# 06_DDR_CONTROLLER.net
KiCad netlist of a schematic drawn in Altium Designer
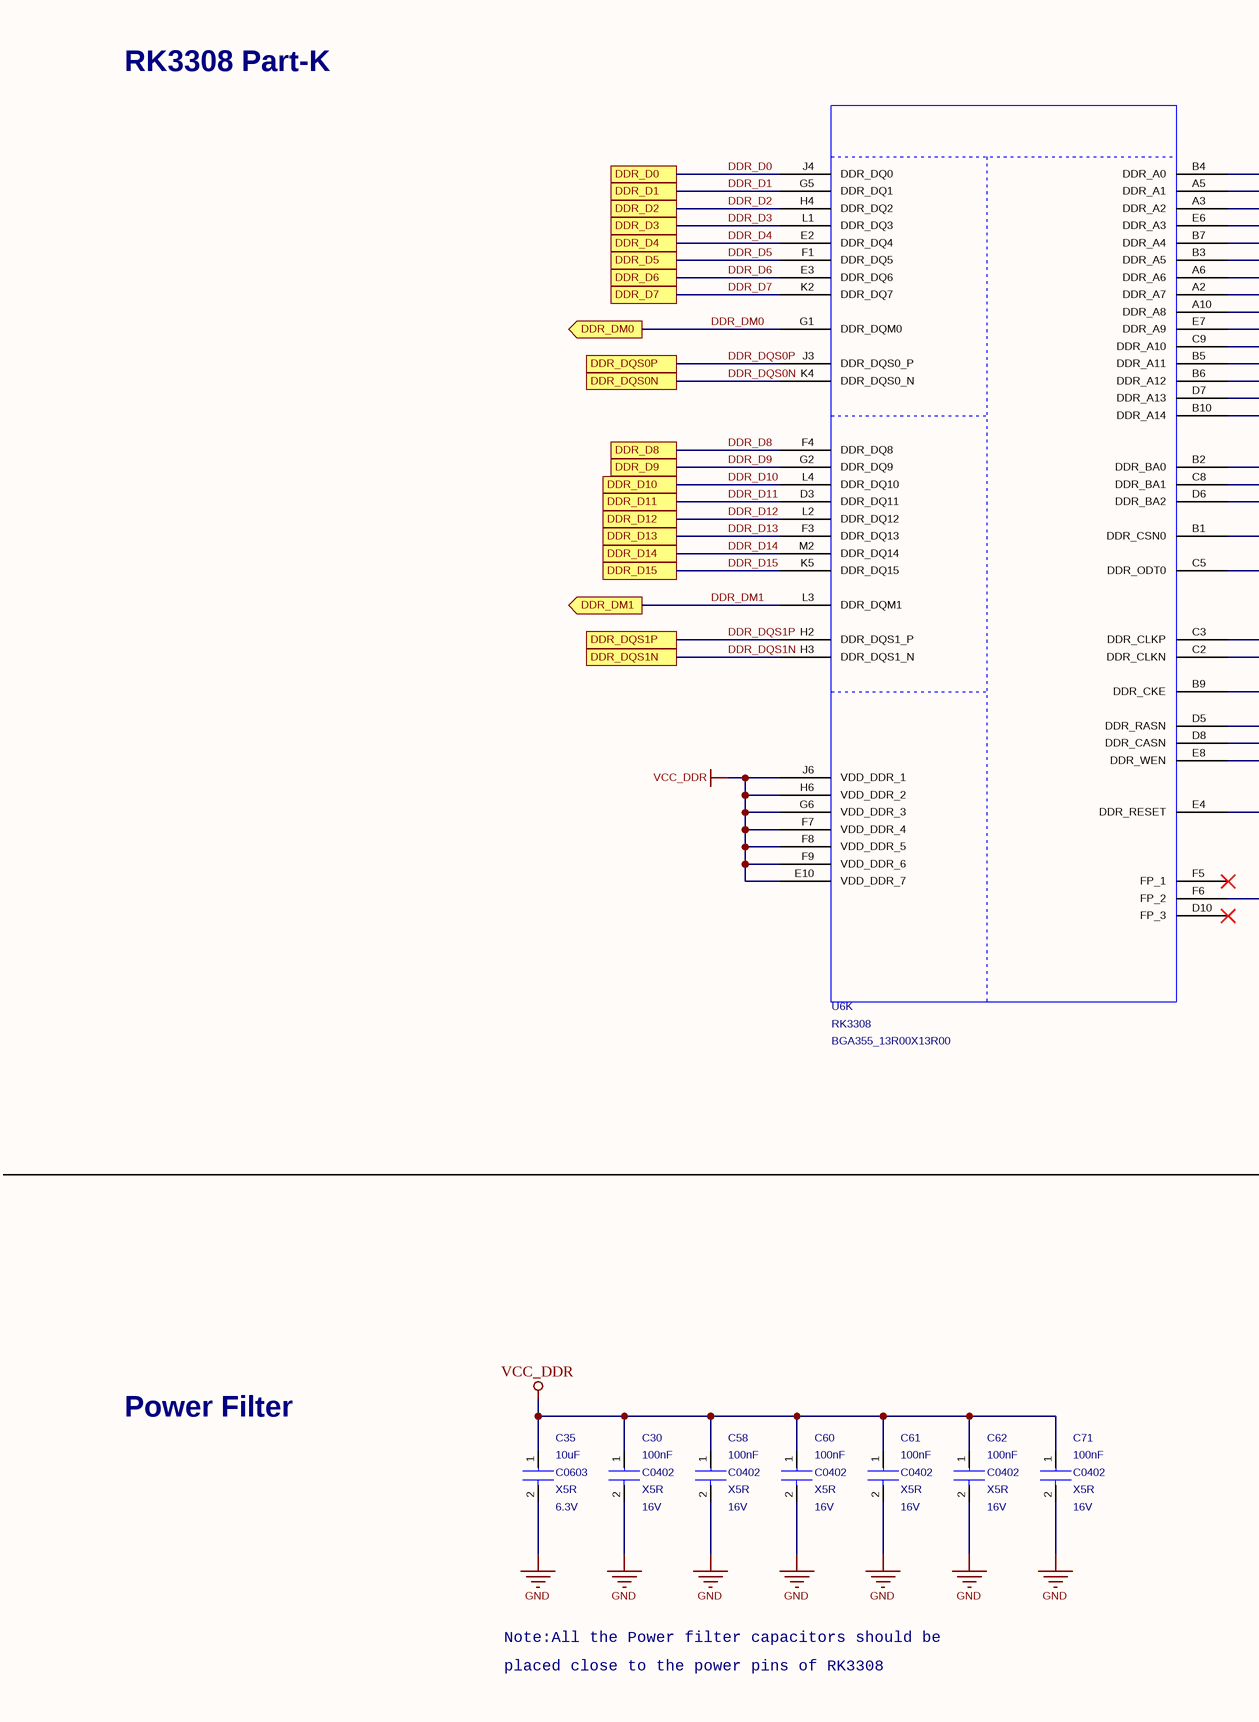
[diagram p0: 06_DDR_CONTROLLER.SchDoc, left]
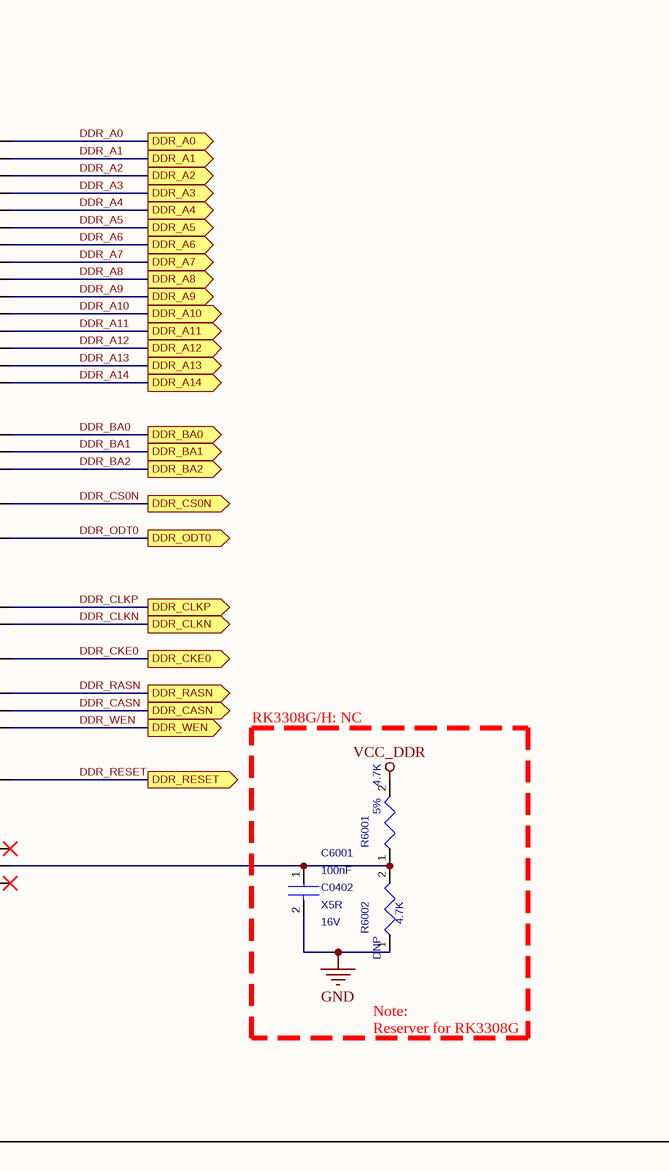
[diagram p1: 06_DDR_CONTROLLER.SchDoc, right]

(export (version "E")
  (design (tool "Eeschema 10.0.6"))
  (components
    (comp (ref "C30")
      (value "100nF")
      (footprint "C0402")
      (description "cap,100.00nF,+/-10%,16V,X5R,C0402")
      (fields
        (field (name "PCB DECAL") "C0402")
        (field (name "MANUFACTURER") "TDK")
        (field (name "TOLERANCE") "10%")
        (field (name "VOLTAGE") "16V")
        (field (name "DIELECTRIC") "X5R")
        (field (name "CREATED_BY") "JJJ")
      )
      (libsource (lib "*") (part "CAP_NP_2"))
    )
    (comp (ref "C35")
      (value "10uF")
      (footprint "C0603")
      (description "cap,10.00uF,+/-10%,6.3V,X5R,C0603")
      (fields
        (field (name "PCB DECAL") "C0603")
        (field (name "DIELECTRIC") "X5R")
        (field (name "VOLTAGE") "6.3V")
        (field (name "TOLERANCE") "10%")
        (field (name "MANUFACTURER") "TDK")
        (field (name "CREATED_BY") "JJJ")
      )
      (libsource (lib "*") (part "CAP_NP_2"))
    )
    (comp (ref "C58")
      (value "100nF")
      (footprint "C0402")
      (description "cap,100.00nF,+/-10%,16V,X5R,C0402")
      (fields
        (field (name "PCB DECAL") "C0402")
        (field (name "DIELECTRIC") "X5R")
        (field (name "VOLTAGE") "16V")
        (field (name "TOLERANCE") "10%")
        (field (name "MANUFACTURER") "TDK")
        (field (name "CREATED_BY") "JJJ")
      )
      (libsource (lib "*") (part "CAP_NP_2"))
    )
    (comp (ref "C60")
      (value "100nF")
      (footprint "C0402")
      (description "cap,100.00nF,+/-10%,16V,X5R,C0402")
      (fields
        (field (name "PCB DECAL") "C0402")
        (field (name "MANUFACTURER") "TDK")
        (field (name "TOLERANCE") "10%")
        (field (name "VOLTAGE") "16V")
        (field (name "DIELECTRIC") "X5R")
        (field (name "CREATED_BY") "JJJ")
      )
      (libsource (lib "*") (part "CAP_NP_2"))
    )
    (comp (ref "C61")
      (value "100nF")
      (footprint "C0402")
      (description "cap,100.00nF,+/-10%,16V,X5R,C0402")
      (fields
        (field (name "PCB DECAL") "C0402")
        (field (name "MANUFACTURER") "TDK")
        (field (name "TOLERANCE") "10%")
        (field (name "VOLTAGE") "16V")
        (field (name "DIELECTRIC") "X5R")
        (field (name "CREATED_BY") "JJJ")
      )
      (libsource (lib "*") (part "CAP_NP_2"))
    )
    (comp (ref "C62")
      (value "100nF")
      (footprint "C0402")
      (description "cap,100.00nF,+/-10%,16V,X5R,C0402")
      (fields
        (field (name "PCB DECAL") "C0402")
        (field (name "MANUFACTURER") "TDK")
        (field (name "TOLERANCE") "10%")
        (field (name "VOLTAGE") "16V")
        (field (name "DIELECTRIC") "X5R")
        (field (name "CREATED_BY") "JJJ")
      )
      (libsource (lib "*") (part "CAP_NP_2"))
    )
    (comp (ref "C71")
      (value "100nF")
      (footprint "C0402")
      (description "cap,100.00nF,+/-10%,16V,X5R,C0402")
      (fields
        (field (name "PCB DECAL") "C0402")
        (field (name "MANUFACTURER") "TDK")
        (field (name "TOLERANCE") "10%")
        (field (name "VOLTAGE") "16V")
        (field (name "DIELECTRIC") "X5R")
        (field (name "CREATED_BY") "JJJ")
      )
      (libsource (lib "*") (part "CAP_NP_2"))
    )
    (comp (ref "C6001")
      (value "100nF")
      (footprint "C0402")
      (description "cap,100.00nF,+/-10%,16V,X5R,C0402")
      (fields
        (field (name "PCB DECAL") "C0402")
        (field (name "MANUFACTURER") "TDK")
        (field (name "TOLERANCE") "10%")
        (field (name "VOLTAGE") "16V")
        (field (name "DIELECTRIC") "X5R")
        (field (name "CREATED_BY") "JJJ")
      )
      (libsource (lib "*") (part "CAP_NP_2"))
    )
    (comp (ref "R6001")
      (value "4.7K")
      (footprint "R0402")
      (description "?用厚膜电阻,4K7,+/-5%,R0402,1/16W.")
      (fields
        (field (name "MANUFACTURER") "YAGEO")
        (field (name "TOLERANCE") "5%")
        (field (name "CREATED_BY") "YTL")
      )
      (libsource (lib "*") (part "RESISTOR"))
    )
    (comp (ref "R6002")
      (value "4.7K")
      (footprint "R0402")
      (description "?用厚膜电阻,4K7,+/-5%,R0402,1/16W.")
      (fields
        (field (name "MANUFACTURER") "YAGEO")
        (field (name "TOLERANCE") "5%")
        (field (name "OPTION") "DNP")
        (field (name "Comment") "RESISTOR")
        (field (name "CREATED_BY") "YTL")
      )
      (libsource (lib "*") (part "RESISTOR"))
    )
    (comp (ref "U6")
      (value "RK3308")
      (footprint "BGA355_13R00X13R00")
      (fields (field (name "PCB DECAL") "BGA355_13R00X13R00") (field (name "MANUFACTURER") "ROCKCHIP"))
      (libsource (lib "*") (part "RK3308"))
    )
  )
  (nets
    (net (code "1") (name "/DDR_A0") (class "Default")
      (node (ref "U6") (pin "B4") (pinfunction "DDR_A0_B4") (pintype "passive"))
    )
    (net (code "2") (name "/DDR_A1") (class "Default")
      (node (ref "U6") (pin "A5") (pinfunction "DDR_A1_A5") (pintype "passive"))
    )
    (net (code "3") (name "/DDR_A2") (class "Default")
      (node (ref "U6") (pin "A3") (pinfunction "DDR_A2_A3") (pintype "passive"))
    )
    (net (code "4") (name "/DDR_A3") (class "Default")
      (node (ref "U6") (pin "E6") (pinfunction "DDR_A3_E6") (pintype "passive"))
    )
    (net (code "5") (name "/DDR_A4") (class "Default")
      (node (ref "U6") (pin "B7") (pinfunction "DDR_A4_B7") (pintype "passive"))
    )
    (net (code "6") (name "/DDR_A5") (class "Default")
      (node (ref "U6") (pin "B3") (pinfunction "DDR_A5_B3") (pintype "passive"))
    )
    (net (code "7") (name "/DDR_A6") (class "Default")
      (node (ref "U6") (pin "A6") (pinfunction "DDR_A6_A6") (pintype "passive"))
    )
    (net (code "8") (name "/DDR_A7") (class "Default")
      (node (ref "U6") (pin "A2") (pinfunction "DDR_A7_A2") (pintype "passive"))
    )
    (net (code "9") (name "/DDR_A8") (class "Default")
      (node (ref "U6") (pin "A10") (pinfunction "DDR_A8_A10") (pintype "passive"))
    )
    (net (code "10") (name "/DDR_A9") (class "Default")
      (node (ref "U6") (pin "E7") (pinfunction "DDR_A9_E7") (pintype "passive"))
    )
    (net (code "11") (name "/DDR_A10") (class "Default")
      (node (ref "U6") (pin "C9") (pinfunction "DDR_A10_C9") (pintype "passive"))
    )
    (net (code "12") (name "/DDR_A11") (class "Default")
      (node (ref "U6") (pin "B5") (pinfunction "DDR_A11_B5") (pintype "passive"))
    )
    (net (code "13") (name "/DDR_A12") (class "Default")
      (node (ref "U6") (pin "B6") (pinfunction "DDR_A12_B6") (pintype "passive"))
    )
    (net (code "14") (name "/DDR_A13") (class "Default")
      (node (ref "U6") (pin "D7") (pinfunction "DDR_A13_D7") (pintype "passive"))
    )
    (net (code "15") (name "/DDR_A14") (class "Default")
      (node (ref "U6") (pin "B10") (pinfunction "DDR_A14_B10") (pintype "passive"))
    )
    (net (code "16") (name "/DDR_BA0") (class "Default")
      (node (ref "U6") (pin "B2") (pinfunction "DDR_BA0_B2") (pintype "passive"))
    )
    (net (code "17") (name "/DDR_BA1") (class "Default")
      (node (ref "U6") (pin "C8") (pinfunction "DDR_BA1_C8") (pintype "passive"))
    )
    (net (code "18") (name "/DDR_BA2") (class "Default")
      (node (ref "U6") (pin "D6") (pinfunction "DDR_BA2_D6") (pintype "passive"))
    )
    (net (code "19") (name "/DDR_CASN") (class "Default")
      (node (ref "U6") (pin "D8") (pinfunction "DDR_CASN_D8") (pintype "passive"))
    )
    (net (code "20") (name "/DDR_CKE0") (class "Default")
      (node (ref "U6") (pin "B9") (pinfunction "DDR_CKE_B9") (pintype "passive"))
    )
    (net (code "21") (name "/DDR_CLKN") (class "Default")
      (node (ref "U6") (pin "C2") (pinfunction "DDR_CLKN_C2") (pintype "passive"))
    )
    (net (code "22") (name "/DDR_CLKP") (class "Default")
      (node (ref "U6") (pin "C3") (pinfunction "DDR_CLKP_C3") (pintype "passive"))
    )
    (net (code "23") (name "/DDR_CS0N") (class "Default")
      (node (ref "U6") (pin "B1") (pinfunction "DDR_CSN0_B1") (pintype "passive"))
    )
    (net (code "24") (name "/DDR_D0") (class "Default")
      (node (ref "U6") (pin "J4") (pinfunction "DDR_DQ0_J4") (pintype "passive"))
    )
    (net (code "25") (name "/DDR_D1") (class "Default")
      (node (ref "U6") (pin "G5") (pinfunction "DDR_DQ1_G5") (pintype "passive"))
    )
    (net (code "26") (name "/DDR_D2") (class "Default")
      (node (ref "U6") (pin "H4") (pinfunction "DDR_DQ2_H4") (pintype "passive"))
    )
    (net (code "27") (name "/DDR_D3") (class "Default")
      (node (ref "U6") (pin "L1") (pinfunction "DDR_DQ3_L1") (pintype "passive"))
    )
    (net (code "28") (name "/DDR_D4") (class "Default")
      (node (ref "U6") (pin "E2") (pinfunction "DDR_DQ4_E2") (pintype "passive"))
    )
    (net (code "29") (name "/DDR_D5") (class "Default")
      (node (ref "U6") (pin "F1") (pinfunction "DDR_DQ5_F1") (pintype "passive"))
    )
    (net (code "30") (name "/DDR_D6") (class "Default")
      (node (ref "U6") (pin "E3") (pinfunction "DDR_DQ6_E3") (pintype "passive"))
    )
    (net (code "31") (name "/DDR_D7") (class "Default")
      (node (ref "U6") (pin "K2") (pinfunction "DDR_DQ7_K2") (pintype "passive"))
    )
    (net (code "32") (name "/DDR_D8") (class "Default")
      (node (ref "U6") (pin "F4") (pinfunction "DDR_DQ8_F4") (pintype "passive"))
    )
    (net (code "33") (name "/DDR_D9") (class "Default")
      (node (ref "U6") (pin "G2") (pinfunction "DDR_DQ9_G2") (pintype "passive"))
    )
    (net (code "34") (name "/DDR_D10") (class "Default")
      (node (ref "U6") (pin "L4") (pinfunction "DDR_DQ10_L4") (pintype "passive"))
    )
    (net (code "35") (name "/DDR_D11") (class "Default")
      (node (ref "U6") (pin "D3") (pinfunction "DDR_DQ11_D3") (pintype "passive"))
    )
    (net (code "36") (name "/DDR_D12") (class "Default")
      (node (ref "U6") (pin "L2") (pinfunction "DDR_DQ12_L2") (pintype "passive"))
    )
    (net (code "37") (name "/DDR_D13") (class "Default")
      (node (ref "U6") (pin "F3") (pinfunction "DDR_DQ13_F3") (pintype "passive"))
    )
    (net (code "38") (name "/DDR_D14") (class "Default")
      (node (ref "U6") (pin "M2") (pinfunction "DDR_DQ14_M2") (pintype "passive"))
    )
    (net (code "39") (name "/DDR_D15") (class "Default")
      (node (ref "U6") (pin "K5") (pinfunction "DDR_DQ15_K5") (pintype "passive"))
    )
    (net (code "40") (name "/DDR_DM0") (class "Default")
      (node (ref "U6") (pin "G1") (pinfunction "DDR_DQM0_G1") (pintype "passive"))
    )
    (net (code "41") (name "/DDR_DM1") (class "Default")
      (node (ref "U6") (pin "L3") (pinfunction "DDR_DQM1_L3") (pintype "passive"))
    )
    (net (code "42") (name "/DDR_DQS0N") (class "Default")
      (node (ref "U6") (pin "K4") (pinfunction "DDR_DQS0_N_K4") (pintype "passive"))
    )
    (net (code "43") (name "/DDR_DQS0P") (class "Default")
      (node (ref "U6") (pin "J3") (pinfunction "DDR_DQS0_P_J3") (pintype "passive"))
    )
    (net (code "44") (name "/DDR_DQS1N") (class "Default")
      (node (ref "U6") (pin "H3") (pinfunction "DDR_DQS1_N_H3") (pintype "passive"))
    )
    (net (code "45") (name "/DDR_DQS1P") (class "Default")
      (node (ref "U6") (pin "H2") (pinfunction "DDR_DQS1_P_H2") (pintype "passive"))
    )
    (net (code "46") (name "/DDR_ODT0") (class "Default")
      (node (ref "U6") (pin "C5") (pinfunction "DDR_ODT0_C5") (pintype "passive"))
    )
    (net (code "47") (name "/DDR_RASN") (class "Default")
      (node (ref "U6") (pin "D5") (pinfunction "DDR_RASN_D5") (pintype "passive"))
    )
    (net (code "48") (name "/DDR_RESET") (class "Default")
      (node (ref "U6") (pin "E4") (pinfunction "DDR_RESET_E4") (pintype "passive"))
    )
    (net (code "49") (name "/DDR_WEN") (class "Default")
      (node (ref "U6") (pin "E8") (pinfunction "DDR_WEN_E8") (pintype "passive"))
    )
    (net (code "50") (name "GND") (class "Default")
      (node (ref "C30") (pin "2") (pinfunction "2_2") (pintype "passive"))
      (node (ref "C35") (pin "2") (pinfunction "2_2") (pintype "passive"))
      (node (ref "C58") (pin "2") (pinfunction "2_2") (pintype "passive"))
      (node (ref "C60") (pin "2") (pinfunction "2_2") (pintype "passive"))
      (node (ref "C6001") (pin "2") (pinfunction "2_2") (pintype "passive"))
      (node (ref "C61") (pin "2") (pinfunction "2_2") (pintype "passive"))
      (node (ref "C62") (pin "2") (pinfunction "2_2") (pintype "passive"))
      (node (ref "C71") (pin "2") (pinfunction "2_2") (pintype "passive"))
      (node (ref "R6002") (pin "1") (pinfunction "1_1") (pintype "passive"))
    )
    (net (code "51") (name "Net-(U6K-FP_2)") (class "Default")
      (node (ref "C6001") (pin "1") (pinfunction "1_1") (pintype "passive"))
      (node (ref "R6001") (pin "1") (pinfunction "1_1") (pintype "passive"))
      (node (ref "R6002") (pin "2") (pinfunction "2_2") (pintype "passive"))
      (node (ref "U6") (pin "F6") (pinfunction "FP_2_F6") (pintype "passive"))
    )
    (net (code "52") (name "VCC_DDR") (class "Default")
      (node (ref "C30") (pin "1") (pinfunction "1_1") (pintype "passive"))
      (node (ref "C35") (pin "1") (pinfunction "1_1") (pintype "passive"))
      (node (ref "C58") (pin "1") (pinfunction "1_1") (pintype "passive"))
      (node (ref "C60") (pin "1") (pinfunction "1_1") (pintype "passive"))
      (node (ref "C61") (pin "1") (pinfunction "1_1") (pintype "passive"))
      (node (ref "C62") (pin "1") (pinfunction "1_1") (pintype "passive"))
      (node (ref "C71") (pin "1") (pinfunction "1_1") (pintype "passive"))
      (node (ref "R6001") (pin "2") (pinfunction "2_2") (pintype "passive"))
      (node (ref "U6") (pin "E10") (pinfunction "VDD_DDR_7_E10") (pintype "power_in"))
      (node (ref "U6") (pin "F7") (pinfunction "VDD_DDR_4_F7") (pintype "power_in"))
      (node (ref "U6") (pin "F8") (pinfunction "VDD_DDR_5_F8") (pintype "power_in"))
      (node (ref "U6") (pin "F9") (pinfunction "VDD_DDR_6_F9") (pintype "power_in"))
      (node (ref "U6") (pin "G6") (pinfunction "VDD_DDR_3_G6") (pintype "power_in"))
      (node (ref "U6") (pin "H6") (pinfunction "VDD_DDR_2_H6") (pintype "power_in"))
      (node (ref "U6") (pin "J6") (pinfunction "VDD_DDR_1_J6") (pintype "power_in"))
    )
    (net (code "53") (name "unconnected-(U6K-FP_1-PadF5)") (class "Default")
      (node (ref "U6") (pin "F5") (pinfunction "FP_1_F5") (pintype "passive+no_connect"))
    )
    (net (code "54") (name "unconnected-(U6K-FP_3-PadD10)") (class "Default")
      (node (ref "U6") (pin "D10") (pinfunction "FP_3_D10") (pintype "passive+no_connect"))
    )
  )
)
